# NB_IoT.net
KiCad netlist of a schematic drawn in Altium Designer
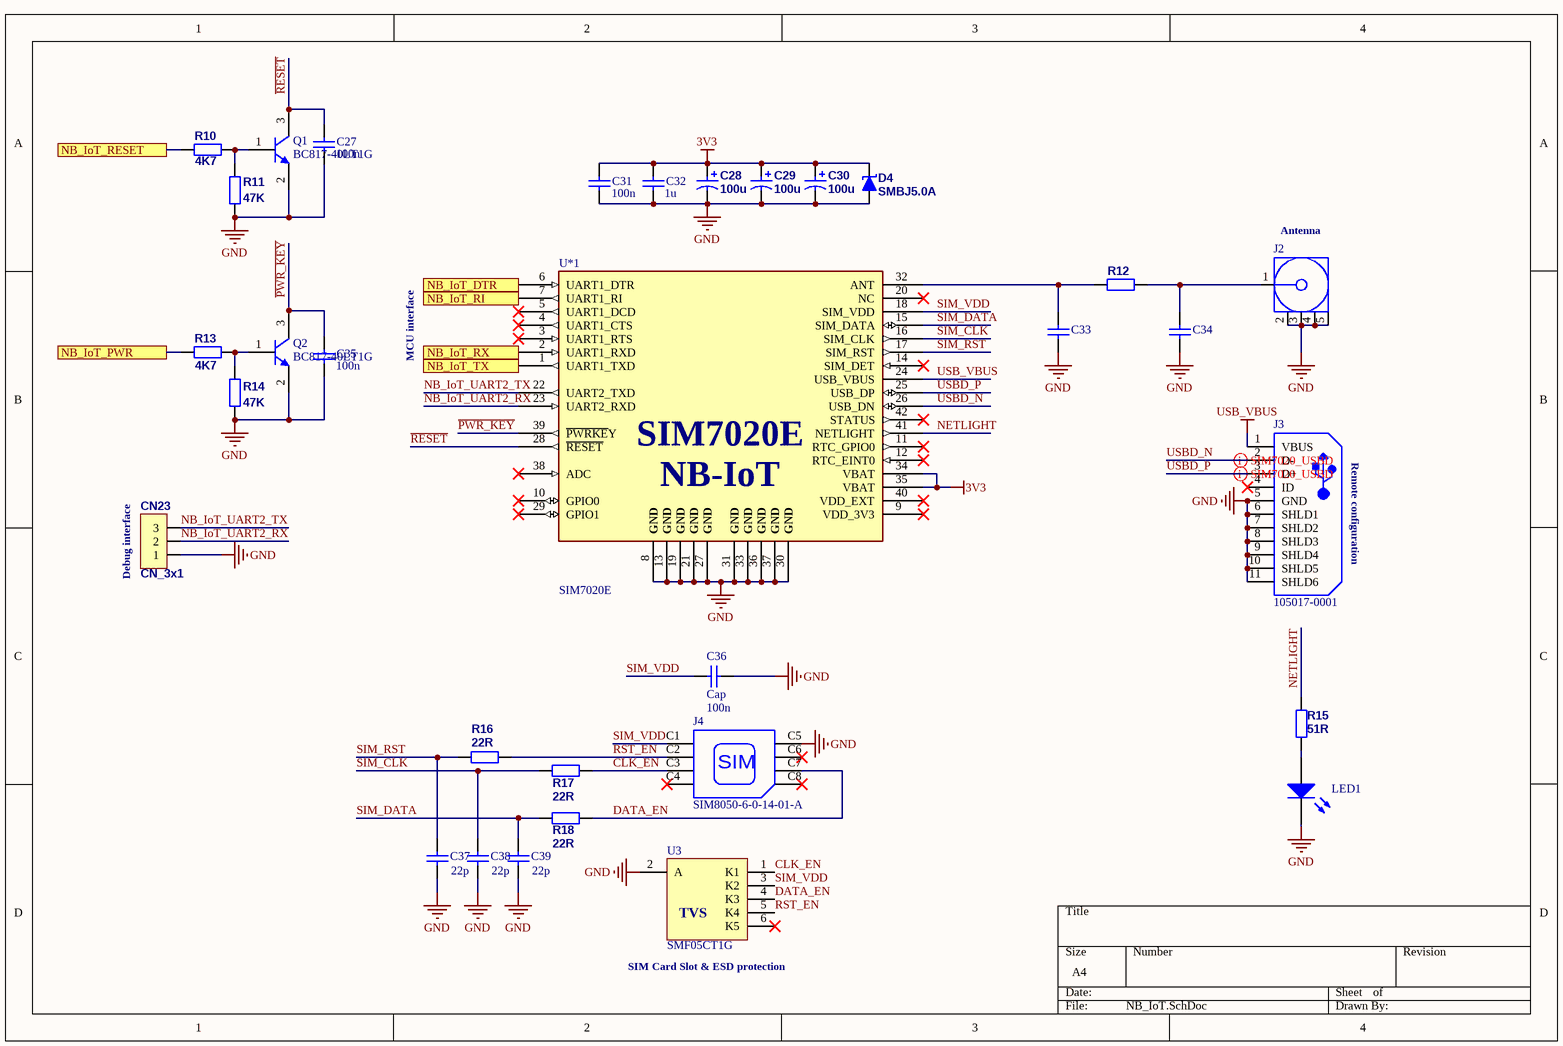
[diagram p0: NB_IoT.SchDoc]

(export (version "E")
  (design (tool "Eeschema 10.0.6"))
  (components
    (comp (ref "C27")
      (value "100n")
      (footprint "0603_CAP_NPOL")
      (description "Capacitor")
      (fields (field (name "Comment") "Cap") (field (name "PUBLISHER") "Altium Limited"))
      (libsource (lib "Miscellaneous Devices") (part "Cap"))
    )
    (comp (ref "C28")
      (value "100u")
      (footprint "0603_CAP_NPOL")
      (description "Polarized Capacitor")
      (libsource (lib "capacitors") (part "Cap Pol"))
    )
    (comp (ref "C29")
      (value "100u")
      (footprint "0603_CAP_NPOL")
      (description "Polarized Capacitor")
      (libsource (lib "capacitors") (part "Cap Pol"))
    )
    (comp (ref "C30")
      (value "100u")
      (footprint "0603_CAP_NPOL")
      (description "Polarized Capacitor")
      (libsource (lib "capacitors") (part "Cap Pol"))
    )
    (comp (ref "C31")
      (value "100n")
      (footprint "0603_CAP_NPOL")
      (description "Capacitor")
      (fields (field (name "Comment") "Cap") (field (name "PUBLISHER") "Altium Limited"))
      (libsource (lib "Miscellaneous Devices") (part "Cap"))
    )
    (comp (ref "C32")
      (value "1u")
      (footprint "0603_CAP_NPOL")
      (description "Capacitor")
      (fields (field (name "Comment") "Cap") (field (name "PUBLISHER") "Altium Limited"))
      (libsource (lib "Miscellaneous Devices") (part "Cap"))
    )
    (comp (ref "C33")
      (value "ap")
      (footprint "0603_CAP_NPOL")
      (description "Capacitor")
      (fields (field (name "PUBLISHER") "Altium Limited"))
      (libsource (lib "Miscellaneous Devices") (part "Cap"))
    )
    (comp (ref "C34")
      (value "ap")
      (footprint "0603_CAP_NPOL")
      (description "Capacitor")
      (fields (field (name "PUBLISHER") "Altium Limited"))
      (libsource (lib "Miscellaneous Devices") (part "Cap"))
    )
    (comp (ref "C35")
      (value "100n")
      (footprint "0603_CAP_NPOL")
      (description "Capacitor")
      (fields (field (name "Comment") "Cap") (field (name "PUBLISHER") "Altium Limited"))
      (libsource (lib "Miscellaneous Devices") (part "Cap"))
    )
    (comp (ref "C36")
      (value "Cap")
      (footprint "0603_CAP_NPOL")
      (description "Capacitor")
      (fields (field (name "ALTIUM_VALUE") "100n") (field (name "PUBLISHER") "Altium Limited"))
      (libsource (lib "Miscellaneous Devices") (part "Cap"))
    )
    (comp (ref "C37")
      (value "22p")
      (footprint "0603_CAP_NPOL")
      (description "Capacitor")
      (fields (field (name "Comment") "Cap") (field (name "PUBLISHER") "Altium Limited"))
      (libsource (lib "Miscellaneous Devices") (part "Cap"))
    )
    (comp (ref "C38")
      (value "22p")
      (footprint "0603_CAP_NPOL")
      (description "Capacitor")
      (fields (field (name "Comment") "Cap") (field (name "PUBLISHER") "Altium Limited"))
      (libsource (lib "Miscellaneous Devices") (part "Cap"))
    )
    (comp (ref "C39")
      (value "22p")
      (footprint "0603_CAP_NPOL")
      (description "Capacitor")
      (fields (field (name "Comment") "Cap") (field (name "PUBLISHER") "Altium Limited"))
      (libsource (lib "Miscellaneous Devices") (part "Cap"))
    )
    (comp (ref "CN23")
      (value "CN_3x1")
      (footprint "GP_3x1_2mm")
      (libsource (lib "goldpin_male") (part "CN_3x1"))
    )
    (comp (ref "D4")
      (value "SMBJ5.0A")
      (footprint "SMB")
      (description "5.0V, 600W Surface Mount Transient Voltage Suppression Diode, SMBJ Series")
      (libsource (lib "diodes_transil") (part "SMBJ5.0A"))
    )
    (comp (ref "J2")
      (value "731000114")
      (footprint "MOLX-731000114_V")
      (description "SMA Right-Angle PCB Jack Receptacle, Brass Body, Gold Plated, 50 Ohm, 5-Pin THD, RoHS, Tray")
      (fields (field (name "MANUFACTURER") "Molex"))
      (libsource (lib "Altium Content Vault") (part "CN-S-4F-RF5"))
    )
    (comp (ref "J3")
      (value "105017-0001")
      (footprint "USB-MICRO-B_V")
      (fields (field (name "MANUFACTURER") "Molex"))
      (libsource (lib "Altium Content Vault") (part "USB-5-6SHLD"))
    )
    (comp (ref "J4")
      (value "SIM8050-6-0-14-01-A")
      (footprint "GCT-SIM8050-6_V")
      (fields (field (name "MANUFACTURER") "Global Connector Technology"))
      (libsource (lib "Altium Content Vault") (part "CN-2P-2F-SIM6"))
    )
    (comp (ref "LED1")
      (value "150080RS75000")
      (footprint "0805_A")
      (description "SMD mono-color Chip LED, WL-SMCW, Red")
      (fields (field (name "MANUFACTURER") "Wuerth Elektronik"))
      (libsource (lib "Altium Content Vault") (part "WE-LED_K1A2-2"))
    )
    (comp (ref "Q1")
      (value "BC817-40LT1G")
      (footprint "ONSC-SOT-23-3-318-08_V")
      (description "General Purpose Transistor, NPN Silicon, 3-Pin SOT-23, Pb-Free, Tape and Reel")
      (fields (field (name "MANUFACTURER") "On Semiconductor"))
      (libsource (lib "Altium Content Vault") (part "ONSC-NPN-B1E2C3-3"))
    )
    (comp (ref "Q2")
      (value "BC817-40LT1G")
      (footprint "ONSC-SOT-23-3-318-08_V")
      (description "General Purpose Transistor, NPN Silicon, 3-Pin SOT-23, Pb-Free, Tape and Reel")
      (fields (field (name "MANUFACTURER") "On Semiconductor"))
      (libsource (lib "Altium Content Vault") (part "ONSC-NPN-B1E2C3-3"))
    )
    (comp (ref "R10")
      (value "4K7")
      (footprint "0402_RES")
      (description "Resistor")
      (libsource (lib "resistors") (part "Res"))
    )
    (comp (ref "R11")
      (value "47K")
      (footprint "0402_RES")
      (description "Resistor")
      (libsource (lib "") (part "Res_1"))
    )
    (comp (ref "R12")
      (value "~")
      (footprint "0402_RES")
      (description "Resistor")
      (libsource (lib "resistors") (part "Res"))
    )
    (comp (ref "R13")
      (value "4K7")
      (footprint "0402_RES")
      (description "Resistor")
      (libsource (lib "resistors") (part "Res"))
    )
    (comp (ref "R14")
      (value "47K")
      (footprint "0402_RES")
      (description "Resistor")
      (libsource (lib "") (part "Res_1"))
    )
    (comp (ref "R15")
      (value "51R")
      (footprint "0402_RES")
      (description "Resistor")
      (libsource (lib "") (part "Res_1"))
    )
    (comp (ref "R16")
      (value "22R")
      (footprint "0402_RES")
      (description "Resistor")
      (libsource (lib "resistors") (part "Res"))
    )
    (comp (ref "R17")
      (value "22R")
      (footprint "0402_RES")
      (description "Resistor")
      (libsource (lib "resistors") (part "Res"))
    )
    (comp (ref "R18")
      (value "22R")
      (footprint "0402_RES")
      (description "Resistor")
      (libsource (lib "resistors") (part "Res"))
    )
    (comp (ref "U*1")
      (value "SIM7020E")
      (footprint "LCC_42PIN")
      (libsource (lib "schematy") (part "SIM7020E"))
    )
    (comp (ref "U3")
      (value "SMF05CT1G")
      (footprint "ONSC-SC70-6-419B-02_W_V")
      (description "5-Line Transient Voltage Suppressor Array, 6-Pin SC70, Pb-Free, Tape and Reel")
      (fields (field (name "MANUFACTURER") "On Semiconductor"))
      (libsource (lib "Altium Content Vault") (part "ONSC-K1A2K3K4K5K6-6"))
    )
  )
  (nets
    (net (code "1") (name "/CLK_EN") (class "Default")
      (node (ref "J4") (pin "C3") (pinfunction "CLK_C3") (pintype "passive"))
      (node (ref "R17") (pin "2") (pinfunction "2_2") (pintype "passive"))
      (node (ref "U3") (pin "1") (pinfunction "K1_1") (pintype "passive"))
    )
    (net (code "2") (name "/DATA_EN") (class "Default")
      (node (ref "J4") (pin "C7") (pinfunction "I/O_C7") (pintype "passive"))
      (node (ref "R18") (pin "2") (pinfunction "2_2") (pintype "passive"))
      (node (ref "U3") (pin "4") (pinfunction "K3_4") (pintype "passive"))
    )
    (net (code "3") (name "/NB_IoT_DTR") (class "Default")
      (node (ref "U*1") (pin "6") (pinfunction "UART1_DTR_6") (pintype "input"))
    )
    (net (code "4") (name "/NB_IoT_PWR") (class "Default")
      (node (ref "R13") (pin "1") (pinfunction "1_1") (pintype "passive"))
    )
    (net (code "5") (name "/NB_IoT_RESET") (class "Default")
      (node (ref "R10") (pin "1") (pinfunction "1_1") (pintype "passive"))
    )
    (net (code "6") (name "/NB_IoT_RI") (class "Default")
      (node (ref "U*1") (pin "7") (pinfunction "UART1_RI_7") (pintype "output"))
    )
    (net (code "7") (name "/NB_IoT_RX") (class "Default")
      (node (ref "U*1") (pin "2") (pinfunction "UART1_RXD_2") (pintype "input"))
    )
    (net (code "8") (name "/NB_IoT_TX") (class "Default")
      (node (ref "U*1") (pin "1") (pinfunction "UART1_TXD_1") (pintype "output"))
    )
    (net (code "9") (name "/NB_IoT_UART2_RX") (class "Default")
      (node (ref "CN23") (pin "2") (pinfunction "2_2") (pintype "passive"))
      (node (ref "U*1") (pin "23") (pinfunction "UART2_RXD_23") (pintype "input"))
    )
    (net (code "10") (name "/NB_IoT_UART2_TX") (class "Default")
      (node (ref "CN23") (pin "3") (pinfunction "3_3") (pintype "passive"))
      (node (ref "U*1") (pin "22") (pinfunction "UART2_TXD_22") (pintype "output"))
    )
    (net (code "11") (name "/NETLIGHT") (class "Default")
      (node (ref "R15") (pin "2") (pinfunction "2_2") (pintype "passive"))
      (node (ref "U*1") (pin "41") (pinfunction "NETLIGHT_41") (pintype "output"))
    )
    (net (code "12") (name "/RST_EN") (class "Default")
      (node (ref "J4") (pin "C2") (pinfunction "RST_C2") (pintype "passive"))
      (node (ref "R16") (pin "2") (pinfunction "2_2") (pintype "passive"))
      (node (ref "U3") (pin "5") (pinfunction "K4_5") (pintype "passive"))
    )
    (net (code "13") (name "/SIM_CLK") (class "Default")
      (node (ref "C38") (pin "2") (pinfunction "2_2") (pintype "passive"))
      (node (ref "R17") (pin "1") (pinfunction "1_1") (pintype "passive"))
      (node (ref "U*1") (pin "16") (pinfunction "SIM_CLK_16") (pintype "output"))
    )
    (net (code "14") (name "/SIM_DATA") (class "Default")
      (node (ref "C39") (pin "2") (pinfunction "2_2") (pintype "passive"))
      (node (ref "R18") (pin "1") (pinfunction "1_1") (pintype "passive"))
      (node (ref "U*1") (pin "15") (pinfunction "SIM_DATA_15") (pintype "bidirectional"))
    )
    (net (code "15") (name "/SIM_RST") (class "Default")
      (node (ref "C37") (pin "2") (pinfunction "2_2") (pintype "passive"))
      (node (ref "R16") (pin "1") (pinfunction "1_1") (pintype "passive"))
      (node (ref "U*1") (pin "17") (pinfunction "SIM_RST_17") (pintype "output"))
    )
    (net (code "16") (name "/SIM_VDD") (class "Default")
      (node (ref "C36") (pin "1") (pinfunction "1_1") (pintype "passive"))
      (node (ref "J4") (pin "C1") (pinfunction "VCC_C1") (pintype "power_in"))
      (node (ref "U*1") (pin "18") (pinfunction "SIM_VDD_18") (pintype "power_in"))
      (node (ref "U3") (pin "3") (pinfunction "K2_3") (pintype "passive"))
    )
    (net (code "17") (name "/USBD_N") (class "Default")
      (node (ref "J3") (pin "2") (pinfunction "D-_2") (pintype "passive"))
      (node (ref "U*1") (pin "26") (pinfunction "USB_DN_26") (pintype "bidirectional"))
    )
    (net (code "18") (name "/USBD_P") (class "Default")
      (node (ref "J3") (pin "3") (pinfunction "D+_3") (pintype "passive"))
      (node (ref "U*1") (pin "25") (pinfunction "USB_DP_25") (pintype "bidirectional"))
    )
    (net (code "19") (name "/~{PWR_KEY}") (class "Default")
      (node (ref "C35") (pin "2") (pinfunction "2_2") (pintype "passive"))
      (node (ref "Q2") (pin "3") (pinfunction "C_3") (pintype "passive"))
      (node (ref "U*1") (pin "39") (pinfunction "~{PWRKE}Y_39") (pintype "output"))
    )
    (net (code "20") (name "/~{RESET}") (class "Default")
      (node (ref "C27") (pin "2") (pinfunction "2_2") (pintype "passive"))
      (node (ref "Q1") (pin "3") (pinfunction "C_3") (pintype "passive"))
      (node (ref "U*1") (pin "28") (pinfunction "~{RESET}_28") (pintype "output"))
    )
    (net (code "21") (name "3V3") (class "Default")
      (node (ref "C28") (pin "1") (pinfunction "1_1") (pintype "passive"))
      (node (ref "C29") (pin "1") (pinfunction "1_1") (pintype "passive"))
      (node (ref "C30") (pin "1") (pinfunction "1_1") (pintype "passive"))
      (node (ref "C31") (pin "2") (pinfunction "2_2") (pintype "passive"))
      (node (ref "C32") (pin "2") (pinfunction "2_2") (pintype "passive"))
      (node (ref "D4") (pin "2") (pinfunction "K_2") (pintype "passive"))
      (node (ref "U*1") (pin "34") (pinfunction "VBAT_34") (pintype "power_in"))
      (node (ref "U*1") (pin "35") (pinfunction "VBAT_35") (pintype "power_in"))
    )
    (net (code "22") (name "GND") (class "Default")
      (node (ref "C27") (pin "1") (pinfunction "1_1") (pintype "passive"))
      (node (ref "C28") (pin "2") (pinfunction "2_2") (pintype "passive"))
      (node (ref "C29") (pin "2") (pinfunction "2_2") (pintype "passive"))
      (node (ref "C30") (pin "2") (pinfunction "2_2") (pintype "passive"))
      (node (ref "C31") (pin "1") (pinfunction "1_1") (pintype "passive"))
      (node (ref "C32") (pin "1") (pinfunction "1_1") (pintype "passive"))
      (node (ref "C33") (pin "1") (pinfunction "1_1") (pintype "passive"))
      (node (ref "C34") (pin "1") (pinfunction "1_1") (pintype "passive"))
      (node (ref "C35") (pin "1") (pinfunction "1_1") (pintype "passive"))
      (node (ref "C36") (pin "2") (pinfunction "2_2") (pintype "passive"))
      (node (ref "C37") (pin "1") (pinfunction "1_1") (pintype "passive"))
      (node (ref "C38") (pin "1") (pinfunction "1_1") (pintype "passive"))
      (node (ref "C39") (pin "1") (pinfunction "1_1") (pintype "passive"))
      (node (ref "CN23") (pin "1") (pinfunction "1_1") (pintype "passive"))
      (node (ref "D4") (pin "1") (pinfunction "A_1") (pintype "passive"))
      (node (ref "J2") (pin "2") (pinfunction "2_2") (pintype "passive"))
      (node (ref "J2") (pin "3") (pinfunction "3_3") (pintype "passive"))
      (node (ref "J2") (pin "4") (pinfunction "4_4") (pintype "passive"))
      (node (ref "J2") (pin "5") (pinfunction "5_5") (pintype "passive"))
      (node (ref "J3") (pin "10") (pinfunction "SHLD5_10") (pintype "passive"))
      (node (ref "J3") (pin "11") (pinfunction "SHLD6_11") (pintype "passive"))
      (node (ref "J3") (pin "5") (pinfunction "GND_5") (pintype "passive"))
      (node (ref "J3") (pin "6") (pinfunction "SHLD1_6") (pintype "passive"))
      (node (ref "J3") (pin "7") (pinfunction "SHLD2_7") (pintype "passive"))
      (node (ref "J3") (pin "8") (pinfunction "SHLD3_8") (pintype "passive"))
      (node (ref "J3") (pin "9") (pinfunction "SHLD4_9") (pintype "passive"))
      (node (ref "J4") (pin "C5") (pinfunction "GND_C5") (pintype "power_in"))
      (node (ref "LED1") (pin "1") (pinfunction "K_1") (pintype "passive"))
      (node (ref "Q1") (pin "2") (pinfunction "E_2") (pintype "passive"))
      (node (ref "Q2") (pin "2") (pinfunction "E_2") (pintype "passive"))
      (node (ref "R11") (pin "1") (pinfunction "1_1") (pintype "passive"))
      (node (ref "R14") (pin "1") (pinfunction "1_1") (pintype "passive"))
      (node (ref "U*1") (pin "13") (pinfunction "GND_13") (pintype "power_in"))
      (node (ref "U*1") (pin "19") (pinfunction "GND_19") (pintype "power_in"))
      (node (ref "U*1") (pin "21") (pinfunction "GND_21") (pintype "power_in"))
      (node (ref "U*1") (pin "27") (pinfunction "GND_27") (pintype "power_in"))
      (node (ref "U*1") (pin "30") (pinfunction "GND_30") (pintype "power_in"))
      (node (ref "U*1") (pin "31") (pinfunction "GND_31") (pintype "power_in"))
      (node (ref "U*1") (pin "33") (pinfunction "GND_33") (pintype "power_in"))
      (node (ref "U*1") (pin "36") (pinfunction "GND_36") (pintype "power_in"))
      (node (ref "U*1") (pin "37") (pinfunction "GND_37") (pintype "power_in"))
      (node (ref "U*1") (pin "8") (pinfunction "GND_8") (pintype "power_in"))
      (node (ref "U3") (pin "2") (pinfunction "A_2") (pintype "passive"))
    )
    (net (code "23") (name "Net-(C34-Pad2)") (class "Default")
      (node (ref "C34") (pin "2") (pinfunction "2_2") (pintype "passive"))
      (node (ref "J2") (pin "1") (pinfunction "1_1") (pintype "passive"))
      (node (ref "R12") (pin "2") (pinfunction "2_2") (pintype "passive"))
    )
    (net (code "24") (name "Net-(LED1-A)") (class "Default")
      (node (ref "LED1") (pin "2") (pinfunction "A_2") (pintype "passive"))
      (node (ref "R15") (pin "1") (pinfunction "1_1") (pintype "passive"))
    )
    (net (code "25") (name "Net-(Q1-B)") (class "Default")
      (node (ref "Q1") (pin "1") (pinfunction "B_1") (pintype "passive"))
      (node (ref "R10") (pin "2") (pinfunction "2_2") (pintype "passive"))
      (node (ref "R11") (pin "2") (pinfunction "2_2") (pintype "passive"))
    )
    (net (code "26") (name "Net-(Q2-B)") (class "Default")
      (node (ref "Q2") (pin "1") (pinfunction "B_1") (pintype "passive"))
      (node (ref "R13") (pin "2") (pinfunction "2_2") (pintype "passive"))
      (node (ref "R14") (pin "2") (pinfunction "2_2") (pintype "passive"))
    )
    (net (code "27") (name "Net-(U*1-ANT)") (class "Default")
      (node (ref "C33") (pin "2") (pinfunction "2_2") (pintype "passive"))
      (node (ref "R12") (pin "1") (pinfunction "1_1") (pintype "passive"))
      (node (ref "U*1") (pin "32") (pinfunction "ANT_32") (pintype "passive"))
    )
    (net (code "28") (name "USB_VBUS") (class "Default")
      (node (ref "J3") (pin "1") (pinfunction "VBUS_1") (pintype "passive"))
      (node (ref "U*1") (pin "24") (pinfunction "USB_VBUS_24") (pintype "power_in"))
    )
    (net (code "29") (name "unconnected-(J3-ID-Pad4)") (class "Default")
      (node (ref "J3") (pin "4") (pinfunction "ID_4") (pintype "passive+no_connect"))
    )
    (net (code "30") (name "unconnected-(J4-SHLD-PadC4)") (class "Default")
      (node (ref "J4") (pin "C4") (pinfunction "SHLD_C4") (pintype "passive+no_connect"))
    )
    (net (code "31") (name "unconnected-(J4-SHLD-PadC8)") (class "Default")
      (node (ref "J4") (pin "C8") (pinfunction "SHLD_C8") (pintype "passive+no_connect"))
    )
    (net (code "32") (name "unconnected-(J4-VPP-PadC6)") (class "Default")
      (node (ref "J4") (pin "C6") (pinfunction "VPP_C6") (pintype "power_in+no_connect"))
    )
    (net (code "33") (name "unconnected-(U*1-ADC-Pad38)") (class "Default")
      (node (ref "U*1") (pin "38") (pinfunction "ADC_38") (pintype "input+no_connect"))
    )
    (net (code "34") (name "unconnected-(U*1-GPIO0-Pad10)") (class "Default")
      (node (ref "U*1") (pin "10") (pinfunction "GPIO0_10") (pintype "bidirectional+no_connect"))
    )
    (net (code "35") (name "unconnected-(U*1-GPIO1-Pad29)") (class "Default")
      (node (ref "U*1") (pin "29") (pinfunction "GPIO1_29") (pintype "bidirectional+no_connect"))
    )
    (net (code "36") (name "unconnected-(U*1-NC-Pad20)") (class "Default")
      (node (ref "U*1") (pin "20") (pinfunction "NC_20") (pintype "passive+no_connect"))
    )
    (net (code "37") (name "unconnected-(U*1-RTC_EINT0-Pad12)") (class "Default")
      (node (ref "U*1") (pin "12") (pinfunction "RTC_EINT0_12") (pintype "input+no_connect"))
    )
    (net (code "38") (name "unconnected-(U*1-RTC_GPIO0-Pad11)") (class "Default")
      (node (ref "U*1") (pin "11") (pinfunction "RTC_GPIO0_11") (pintype "output+no_connect"))
    )
    (net (code "39") (name "unconnected-(U*1-SIM_DET-Pad14)") (class "Default")
      (node (ref "U*1") (pin "14") (pinfunction "SIM_DET_14") (pintype "input+no_connect"))
    )
    (net (code "40") (name "unconnected-(U*1-STATUS-Pad42)") (class "Default")
      (node (ref "U*1") (pin "42") (pinfunction "STATUS_42") (pintype "output+no_connect"))
    )
    (net (code "41") (name "unconnected-(U*1-UART1_CTS-Pad4)") (class "Default")
      (node (ref "U*1") (pin "4") (pinfunction "UART1_CTS_4") (pintype "output+no_connect"))
    )
    (net (code "42") (name "unconnected-(U*1-UART1_DCD-Pad5)") (class "Default")
      (node (ref "U*1") (pin "5") (pinfunction "UART1_DCD_5") (pintype "output+no_connect"))
    )
    (net (code "43") (name "unconnected-(U*1-UART1_RTS-Pad3)") (class "Default")
      (node (ref "U*1") (pin "3") (pinfunction "UART1_RTS_3") (pintype "input+no_connect"))
    )
    (net (code "44") (name "unconnected-(U*1-VDD_3V3-Pad9)") (class "Default")
      (node (ref "U*1") (pin "9") (pinfunction "VDD_3V3_9") (pintype "power_in+no_connect"))
    )
    (net (code "45") (name "unconnected-(U*1-VDD_EXT-Pad40)") (class "Default")
      (node (ref "U*1") (pin "40") (pinfunction "VDD_EXT_40") (pintype "power_in+no_connect"))
    )
    (net (code "46") (name "unconnected-(U3-K5-Pad6)") (class "Default")
      (node (ref "U3") (pin "6") (pinfunction "K5_6") (pintype "passive+no_connect"))
    )
  )
)
